# sdsheet.net
KiCad netlist of a schematic drawn in Altium Designer
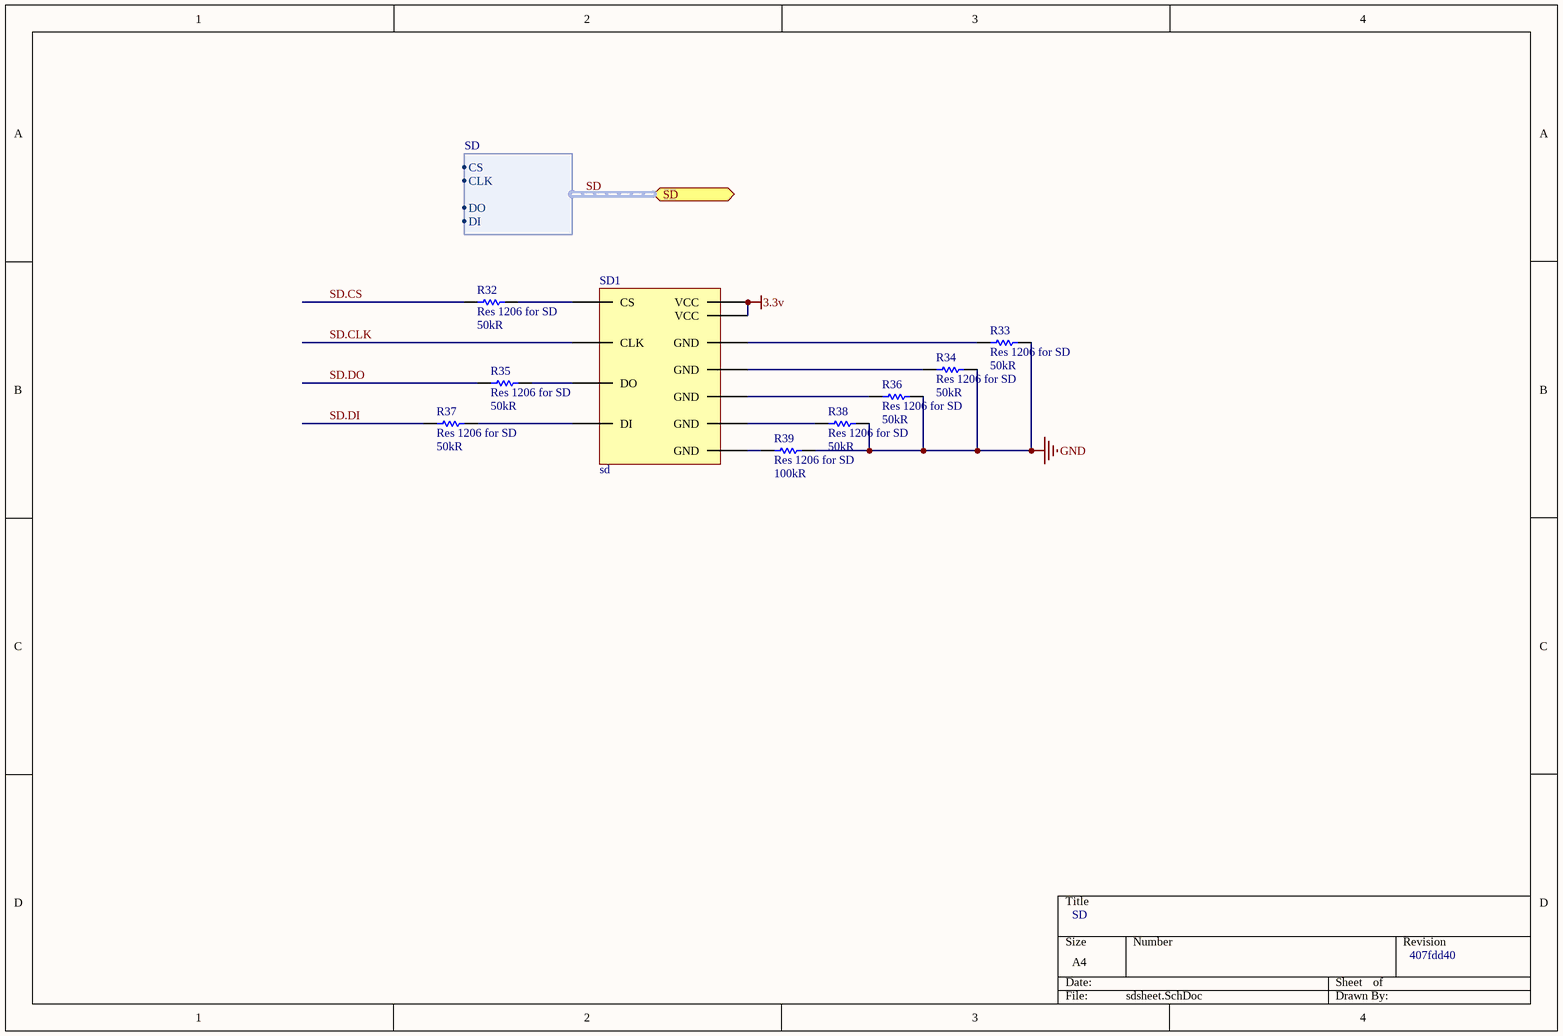
[diagram p0: sdsheet.SchDoc]

(export (version "E")
  (design (tool "Eeschema 10.0.6"))
  (components
    (comp (ref "R32")
      (value "Res 1206 for SD")
      (footprint "RESC1206(3216)_M")
      (description "49K9 0.25W 1% 1206 (3216 Metric)  SMD")
      (fields
        (field (name "TOLERANCE") "1 %")
        (field (name "POWER") "0.25 W")
        (field (name "ALTIUM_VALUE") "50kR")
      )
      (libsource (lib "Altium Content Vault") (part "CMP-1014-00702-1"))
    )
    (comp (ref "R33")
      (value "Res 1206 for SD")
      (footprint "RESC1206(3216)_M")
      (description "49K9 0.25W 1% 1206 (3216 Metric)  SMD")
      (fields
        (field (name "TOLERANCE") "1 %")
        (field (name "POWER") "0.25 W")
        (field (name "ALTIUM_VALUE") "50kR")
      )
      (libsource (lib "Altium Content Vault") (part "CMP-1014-00702-1"))
    )
    (comp (ref "R34")
      (value "Res 1206 for SD")
      (footprint "RESC1206(3216)_M")
      (description "49K9 0.25W 1% 1206 (3216 Metric)  SMD")
      (fields
        (field (name "TOLERANCE") "1 %")
        (field (name "POWER") "0.25 W")
        (field (name "ALTIUM_VALUE") "50kR")
      )
      (libsource (lib "Altium Content Vault") (part "CMP-1014-00702-1"))
    )
    (comp (ref "R35")
      (value "Res 1206 for SD")
      (footprint "RESC1206(3216)_M")
      (description "49K9 0.25W 1% 1206 (3216 Metric)  SMD")
      (fields
        (field (name "TOLERANCE") "1 %")
        (field (name "POWER") "0.25 W")
        (field (name "ALTIUM_VALUE") "50kR")
      )
      (libsource (lib "Altium Content Vault") (part "CMP-1014-00702-1"))
    )
    (comp (ref "R36")
      (value "Res 1206 for SD")
      (footprint "RESC1206(3216)_M")
      (description "49K9 0.25W 1% 1206 (3216 Metric)  SMD")
      (fields
        (field (name "TOLERANCE") "1 %")
        (field (name "POWER") "0.25 W")
        (field (name "ALTIUM_VALUE") "50kR")
      )
      (libsource (lib "Altium Content Vault") (part "CMP-1014-00702-1"))
    )
    (comp (ref "R37")
      (value "Res 1206 for SD")
      (footprint "RESC1206(3216)_M")
      (description "49K9 0.25W 1% 1206 (3216 Metric)  SMD")
      (fields
        (field (name "TOLERANCE") "1 %")
        (field (name "POWER") "0.25 W")
        (field (name "ALTIUM_VALUE") "50kR")
      )
      (libsource (lib "Altium Content Vault") (part "CMP-1014-00702-1"))
    )
    (comp (ref "R38")
      (value "Res 1206 for SD")
      (footprint "RESC1206(3216)_M")
      (description "49K9 0.25W 1% 1206 (3216 Metric)  SMD")
      (fields
        (field (name "TOLERANCE") "1 %")
        (field (name "POWER") "0.25 W")
        (field (name "ALTIUM_VALUE") "50kR")
      )
      (libsource (lib "Altium Content Vault") (part "CMP-1014-00702-1"))
    )
    (comp (ref "R39")
      (value "Res 1206 for SD")
      (footprint "RESC1206(3216)_L")
      (description "100K 0.25W 1% 1206 (3216 Metric)  SMD")
      (fields
        (field (name "TOLERANCE") "1 %")
        (field (name "ALTIUM_VALUE") "100kR")
        (field (name "POWER") "0.25 W")
      )
      (libsource (lib "Altium Content Vault") (part "CMP-1014-00736-1"))
    )
    (comp (ref "SD1")
      (value "sd")
      (footprint "Edge Connector - duplicate1")
      (libsource (lib "librarySDcard") (part "sd"))
    )
  )
  (nets
    (net (code "2") (name "/SD.CLK") (class "Default")
      (node (ref "SD1") (pin "5") (pinfunction "CLK_5") (pintype "passive"))
    )
    (net (code "3") (name "/SD.CS") (class "Default")
      (node (ref "R32") (pin "1") (pinfunction "1_1") (pintype "passive"))
    )
    (net (code "4") (name "/SD.DI") (class "Default")
      (node (ref "R37") (pin "1") (pinfunction "1_1") (pintype "passive"))
    )
    (net (code "5") (name "/SD.DO") (class "Default")
      (node (ref "R35") (pin "1") (pinfunction "1_1") (pintype "passive"))
    )
    (net (code "7") (name "3.3v") (class "Default")
      (node (ref "SD1") (pin "11") (pinfunction "VCC_11") (pintype "passive"))
      (node (ref "SD1") (pin "4") (pinfunction "VCC_4") (pintype "passive"))
    )
    (net (code "8") (name "GND") (class "Default")
      (node (ref "R33") (pin "2") (pinfunction "2_2") (pintype "passive"))
      (node (ref "R34") (pin "2") (pinfunction "2_2") (pintype "passive"))
      (node (ref "R36") (pin "2") (pinfunction "2_2") (pintype "passive"))
      (node (ref "R38") (pin "2") (pinfunction "2_2") (pintype "passive"))
      (node (ref "R39") (pin "2") (pinfunction "2_2") (pintype "passive"))
    )
    (net (code "9") (name "Net-(R33-Pad1)") (class "Default")
      (node (ref "R33") (pin "1") (pinfunction "1_1") (pintype "passive"))
      (node (ref "SD1") (pin "3") (pinfunction "GND_3") (pintype "passive"))
    )
    (net (code "10") (name "Net-(R34-Pad1)") (class "Default")
      (node (ref "R34") (pin "1") (pinfunction "1_1") (pintype "passive"))
      (node (ref "SD1") (pin "6") (pinfunction "GND_6") (pintype "passive"))
    )
    (net (code "11") (name "Net-(R36-Pad1)") (class "Default")
      (node (ref "R36") (pin "1") (pinfunction "1_1") (pintype "passive"))
      (node (ref "SD1") (pin "8") (pinfunction "GND_8") (pintype "passive"))
    )
    (net (code "12") (name "Net-(R38-Pad1)") (class "Default")
      (node (ref "R38") (pin "1") (pinfunction "1_1") (pintype "passive"))
      (node (ref "SD1") (pin "10") (pinfunction "GND_10") (pintype "passive"))
    )
    (net (code "13") (name "Net-(R39-Pad1)") (class "Default")
      (node (ref "R39") (pin "1") (pinfunction "1_1") (pintype "passive"))
      (node (ref "SD1") (pin "12") (pinfunction "GND_12") (pintype "passive"))
    )
    (net (code "14") (name "Net-(SD1-CS)") (class "Default")
      (node (ref "R32") (pin "2") (pinfunction "2_2") (pintype "passive"))
      (node (ref "SD1") (pin "1") (pinfunction "CS_1") (pintype "passive"))
    )
    (net (code "15") (name "Net-(SD1-DI)") (class "Default")
      (node (ref "R37") (pin "2") (pinfunction "2_2") (pintype "passive"))
      (node (ref "SD1") (pin "2") (pinfunction "DI_2") (pintype "passive"))
    )
    (net (code "16") (name "Net-(SD1-DO)") (class "Default")
      (node (ref "R35") (pin "2") (pinfunction "2_2") (pintype "passive"))
      (node (ref "SD1") (pin "7") (pinfunction "DO_7") (pintype "passive"))
    )
  )
)
